# center_v1.net
KiCad netlist of a schematic drawn in EAGLE
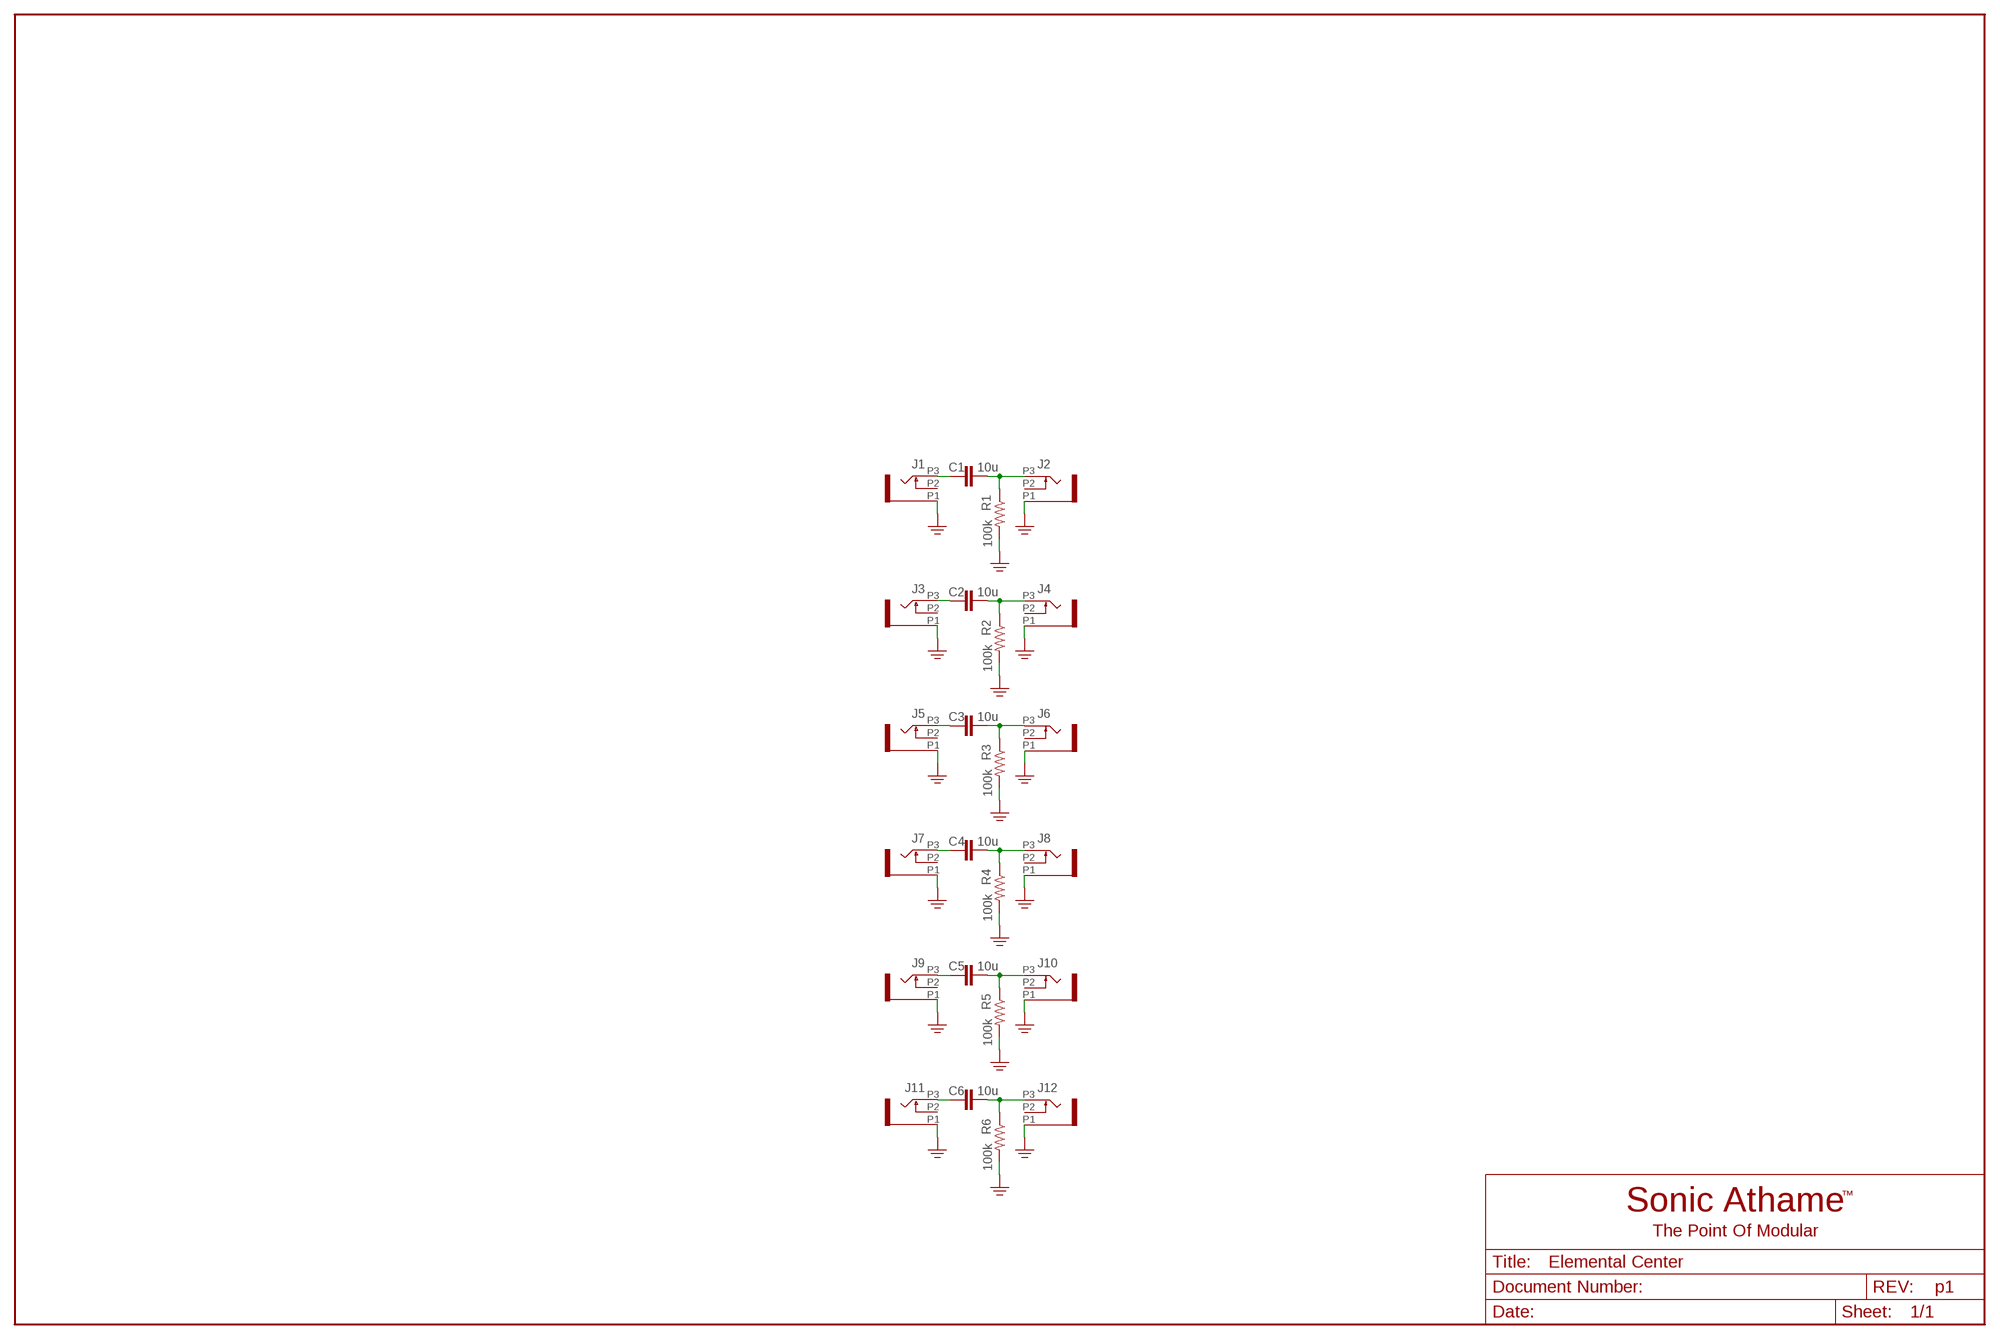
[diagram p0: schematic, sheet 1]

(export (version "E")
  (design (tool "Eeschema 10.0.6"))
  (components
    (comp (ref "C1")
      (value "10u")
      (footprint "eagle-import:C050-024X044")
      (libsource (lib "eagle-import") (part "CAP_NONPOL050-024X044"))
    )
    (comp (ref "C2")
      (value "10u")
      (footprint "eagle-import:C050-024X044")
      (libsource (lib "eagle-import") (part "CAP_NONPOL050-024X044"))
    )
    (comp (ref "C3")
      (value "10u")
      (footprint "eagle-import:C050-024X044")
      (libsource (lib "eagle-import") (part "CAP_NONPOL050-024X044"))
    )
    (comp (ref "C4")
      (value "10u")
      (footprint "eagle-import:C050-024X044")
      (libsource (lib "eagle-import") (part "CAP_NONPOL050-024X044"))
    )
    (comp (ref "C5")
      (value "10u")
      (footprint "eagle-import:C050-024X044")
      (libsource (lib "eagle-import") (part "CAP_NONPOL050-024X044"))
    )
    (comp (ref "C6")
      (value "10u")
      (footprint "eagle-import:C050-024X044")
      (libsource (lib "eagle-import") (part "CAP_NONPOL050-024X044"))
    )
    (comp (ref "J1")
      (value "WQP-PJ398SM6")
      (footprint "eagle-import:WQP_PJ_301M6")
      (libsource (lib "eagle-import") (part "WQP-PJ398SM6"))
    )
    (comp (ref "J2")
      (value "WQP-PJ398SM6")
      (footprint "eagle-import:WQP_PJ_301M6")
      (libsource (lib "eagle-import") (part "WQP-PJ398SM6"))
    )
    (comp (ref "J3")
      (value "WQP-PJ398SM6")
      (footprint "eagle-import:WQP_PJ_301M6")
      (libsource (lib "eagle-import") (part "WQP-PJ398SM6"))
    )
    (comp (ref "J4")
      (value "WQP-PJ398SM6")
      (footprint "eagle-import:WQP_PJ_301M6")
      (libsource (lib "eagle-import") (part "WQP-PJ398SM6"))
    )
    (comp (ref "J5")
      (value "WQP-PJ398SM6")
      (footprint "eagle-import:WQP_PJ_301M6")
      (libsource (lib "eagle-import") (part "WQP-PJ398SM6"))
    )
    (comp (ref "J6")
      (value "WQP-PJ398SM6")
      (footprint "eagle-import:WQP_PJ_301M6")
      (libsource (lib "eagle-import") (part "WQP-PJ398SM6"))
    )
    (comp (ref "J7")
      (value "WQP-PJ398SM6")
      (footprint "eagle-import:WQP_PJ_301M6")
      (libsource (lib "eagle-import") (part "WQP-PJ398SM6"))
    )
    (comp (ref "J8")
      (value "WQP-PJ398SM6")
      (footprint "eagle-import:WQP_PJ_301M6")
      (libsource (lib "eagle-import") (part "WQP-PJ398SM6"))
    )
    (comp (ref "J9")
      (value "WQP-PJ398SM6")
      (footprint "eagle-import:WQP_PJ_301M6")
      (libsource (lib "eagle-import") (part "WQP-PJ398SM6"))
    )
    (comp (ref "J10")
      (value "WQP-PJ398SM6")
      (footprint "eagle-import:WQP_PJ_301M6")
      (libsource (lib "eagle-import") (part "WQP-PJ398SM6"))
    )
    (comp (ref "J11")
      (value "WQP-PJ398SM6")
      (footprint "eagle-import:WQP_PJ_301M6")
      (libsource (lib "eagle-import") (part "WQP-PJ398SM6"))
    )
    (comp (ref "J12")
      (value "WQP-PJ398SM6")
      (footprint "eagle-import:WQP_PJ_301M6")
      (libsource (lib "eagle-import") (part "WQP-PJ398SM6"))
    )
    (comp (ref "R1")
      (value "100k")
      (footprint "eagle-import:0207_2V")
      (libsource (lib "eagle-import") (part "RESISTOR0207/2V"))
    )
    (comp (ref "R2")
      (value "100k")
      (footprint "eagle-import:0207_2V")
      (libsource (lib "eagle-import") (part "RESISTOR0207/2V"))
    )
    (comp (ref "R3")
      (value "100k")
      (footprint "eagle-import:0207_2V")
      (libsource (lib "eagle-import") (part "RESISTOR0207/2V"))
    )
    (comp (ref "R4")
      (value "100k")
      (footprint "eagle-import:0207_2V")
      (libsource (lib "eagle-import") (part "RESISTOR0207/2V"))
    )
    (comp (ref "R5")
      (value "100k")
      (footprint "eagle-import:0207_2V")
      (libsource (lib "eagle-import") (part "RESISTOR0207/2V"))
    )
    (comp (ref "R6")
      (value "100k")
      (footprint "eagle-import:0207_2V")
      (libsource (lib "eagle-import") (part "RESISTOR0207/2V"))
    )
  )
  (nets
    (net (code "1") (name "GND") (class "Default")
      (node (ref "J1") (pin "P1") (pinfunction "1_P1") (pintype "passive"))
      (node (ref "J10") (pin "P1") (pinfunction "1_P1") (pintype "passive"))
      (node (ref "J11") (pin "P1") (pinfunction "1_P1") (pintype "passive"))
      (node (ref "J12") (pin "P1") (pinfunction "1_P1") (pintype "passive"))
      (node (ref "J2") (pin "P1") (pinfunction "1_P1") (pintype "passive"))
      (node (ref "J3") (pin "P1") (pinfunction "1_P1") (pintype "passive"))
      (node (ref "J4") (pin "P1") (pinfunction "1_P1") (pintype "passive"))
      (node (ref "J5") (pin "P1") (pinfunction "1_P1") (pintype "passive"))
      (node (ref "J6") (pin "P1") (pinfunction "1_P1") (pintype "passive"))
      (node (ref "J7") (pin "P1") (pinfunction "1_P1") (pintype "passive"))
      (node (ref "J8") (pin "P1") (pinfunction "1_P1") (pintype "passive"))
      (node (ref "J9") (pin "P1") (pinfunction "1_P1") (pintype "passive"))
      (node (ref "R1") (pin "2") (pinfunction "2_2") (pintype "passive"))
      (node (ref "R2") (pin "2") (pinfunction "2_2") (pintype "passive"))
      (node (ref "R3") (pin "2") (pinfunction "2_2") (pintype "passive"))
      (node (ref "R4") (pin "2") (pinfunction "2_2") (pintype "passive"))
      (node (ref "R5") (pin "2") (pinfunction "2_2") (pintype "passive"))
      (node (ref "R6") (pin "2") (pinfunction "2_2") (pintype "passive"))
    )
    (net (code "2") (name "Net-(J1-3)") (class "Default")
      (node (ref "C1") (pin "1") (pinfunction "1_1") (pintype "passive"))
      (node (ref "J1") (pin "P3") (pinfunction "3_P3") (pintype "passive"))
    )
    (net (code "3") (name "Net-(J2-3)") (class "Default")
      (node (ref "C1") (pin "2") (pinfunction "2_2") (pintype "passive"))
      (node (ref "J2") (pin "P3") (pinfunction "3_P3") (pintype "passive"))
      (node (ref "R1") (pin "1") (pinfunction "1_1") (pintype "passive"))
    )
    (net (code "4") (name "Net-(J3-3)") (class "Default")
      (node (ref "C2") (pin "1") (pinfunction "1_1") (pintype "passive"))
      (node (ref "J3") (pin "P3") (pinfunction "3_P3") (pintype "passive"))
    )
    (net (code "5") (name "Net-(J4-3)") (class "Default")
      (node (ref "C2") (pin "2") (pinfunction "2_2") (pintype "passive"))
      (node (ref "J4") (pin "P3") (pinfunction "3_P3") (pintype "passive"))
      (node (ref "R2") (pin "1") (pinfunction "1_1") (pintype "passive"))
    )
    (net (code "6") (name "Net-(J5-3)") (class "Default")
      (node (ref "C3") (pin "1") (pinfunction "1_1") (pintype "passive"))
      (node (ref "J5") (pin "P3") (pinfunction "3_P3") (pintype "passive"))
    )
    (net (code "7") (name "Net-(J6-3)") (class "Default")
      (node (ref "C3") (pin "2") (pinfunction "2_2") (pintype "passive"))
      (node (ref "J6") (pin "P3") (pinfunction "3_P3") (pintype "passive"))
      (node (ref "R3") (pin "1") (pinfunction "1_1") (pintype "passive"))
    )
    (net (code "8") (name "Net-(J7-3)") (class "Default")
      (node (ref "C4") (pin "1") (pinfunction "1_1") (pintype "passive"))
      (node (ref "J7") (pin "P3") (pinfunction "3_P3") (pintype "passive"))
    )
    (net (code "9") (name "Net-(J8-3)") (class "Default")
      (node (ref "C4") (pin "2") (pinfunction "2_2") (pintype "passive"))
      (node (ref "J8") (pin "P3") (pinfunction "3_P3") (pintype "passive"))
      (node (ref "R4") (pin "1") (pinfunction "1_1") (pintype "passive"))
    )
    (net (code "10") (name "Net-(J9-3)") (class "Default")
      (node (ref "C5") (pin "1") (pinfunction "1_1") (pintype "passive"))
      (node (ref "J9") (pin "P3") (pinfunction "3_P3") (pintype "passive"))
    )
    (net (code "11") (name "Net-(J10-3)") (class "Default")
      (node (ref "C5") (pin "2") (pinfunction "2_2") (pintype "passive"))
      (node (ref "J10") (pin "P3") (pinfunction "3_P3") (pintype "passive"))
      (node (ref "R5") (pin "1") (pinfunction "1_1") (pintype "passive"))
    )
    (net (code "12") (name "Net-(J11-3)") (class "Default")
      (node (ref "C6") (pin "1") (pinfunction "1_1") (pintype "passive"))
      (node (ref "J11") (pin "P3") (pinfunction "3_P3") (pintype "passive"))
    )
    (net (code "13") (name "Net-(J12-3)") (class "Default")
      (node (ref "C6") (pin "2") (pinfunction "2_2") (pintype "passive"))
      (node (ref "J12") (pin "P3") (pinfunction "3_P3") (pintype "passive"))
      (node (ref "R6") (pin "1") (pinfunction "1_1") (pintype "passive"))
    )
    (net (code "14") (name "unconnected-(J1-2-PadP2)") (class "Default")
      (node (ref "J1") (pin "P2") (pinfunction "2_P2") (pintype "passive"))
    )
    (net (code "15") (name "unconnected-(J2-2-PadP2)") (class "Default")
      (node (ref "J2") (pin "P2") (pinfunction "2_P2") (pintype "passive"))
    )
    (net (code "16") (name "unconnected-(J3-2-PadP2)") (class "Default")
      (node (ref "J3") (pin "P2") (pinfunction "2_P2") (pintype "passive"))
    )
    (net (code "17") (name "unconnected-(J4-2-PadP2)") (class "Default")
      (node (ref "J4") (pin "P2") (pinfunction "2_P2") (pintype "passive"))
    )
    (net (code "18") (name "unconnected-(J5-2-PadP2)") (class "Default")
      (node (ref "J5") (pin "P2") (pinfunction "2_P2") (pintype "passive"))
    )
    (net (code "19") (name "unconnected-(J6-2-PadP2)") (class "Default")
      (node (ref "J6") (pin "P2") (pinfunction "2_P2") (pintype "passive"))
    )
    (net (code "20") (name "unconnected-(J7-2-PadP2)") (class "Default")
      (node (ref "J7") (pin "P2") (pinfunction "2_P2") (pintype "passive"))
    )
    (net (code "21") (name "unconnected-(J8-2-PadP2)") (class "Default")
      (node (ref "J8") (pin "P2") (pinfunction "2_P2") (pintype "passive"))
    )
    (net (code "22") (name "unconnected-(J9-2-PadP2)") (class "Default")
      (node (ref "J9") (pin "P2") (pinfunction "2_P2") (pintype "passive"))
    )
    (net (code "23") (name "unconnected-(J10-2-PadP2)") (class "Default")
      (node (ref "J10") (pin "P2") (pinfunction "2_P2") (pintype "passive"))
    )
    (net (code "24") (name "unconnected-(J11-2-PadP2)") (class "Default")
      (node (ref "J11") (pin "P2") (pinfunction "2_P2") (pintype "passive"))
    )
    (net (code "25") (name "unconnected-(J12-2-PadP2)") (class "Default")
      (node (ref "J12") (pin "P2") (pinfunction "2_P2") (pintype "passive"))
    )
  )
)
